# PERIPHERAL_CON.net
KiCad netlist of a schematic drawn in Altium Designer
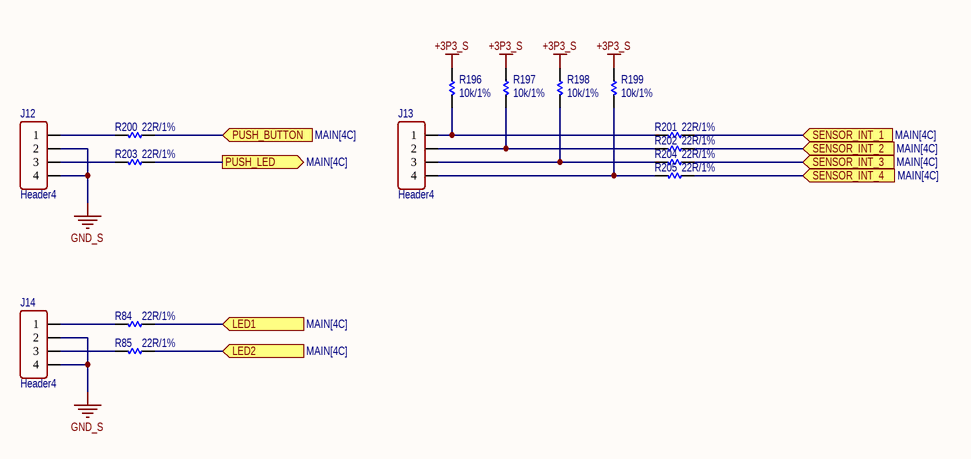
[diagram p0: PERIPHERAL_CON.SchDoc]

(export (version "E")
  (design (tool "Eeschema 10.0.6"))
  (components
    (comp (ref "J12")
      (value "Header4")
      (footprint "XH2.54-4-DIP")
      (description "Connector 4")
      (fields
        (field (name "MANUFACTURER") "Würth Elektronik eiSos GmbH")
        (field (name "PARTNO") "613002143121")
        (field (name "CREATED BY") "Karrer Zheng")
      )
      (libsource (lib "Library") (part "Header4"))
    )
    (comp (ref "J13")
      (value "Header4")
      (footprint "XH2.54-4-DIP")
      (description "Connector 4")
      (fields
        (field (name "MANUFACTURER") "Würth Elektronik eiSos GmbH")
        (field (name "PARTNO") "613002143121")
        (field (name "CREATED BY") "Karrer Zheng")
      )
      (libsource (lib "Library") (part "Header4"))
    )
    (comp (ref "J14")
      (value "Header4")
      (footprint "XH2.54-4-DIP")
      (description "Connector 4")
      (fields
        (field (name "MANUFACTURER") "Würth Elektronik eiSos GmbH")
        (field (name "PARTNO") "613002143121")
        (field (name "CREATED BY") "Karrer Zheng")
      )
      (libsource (lib "Library") (part "Header4"))
    )
    (comp (ref "R84")
      (value "22R/1%")
      (footprint "RES-SMD-0603")
      (description "RES SMD 22 OHM 1% 1/10W 0603")
      (libsource (lib "Library") (part "Res-SMD"))
    )
    (comp (ref "R85")
      (value "22R/1%")
      (footprint "RES-SMD-0603")
      (description "RES SMD 22 OHM 1% 1/10W 0603")
      (libsource (lib "Library") (part "Res-SMD"))
    )
    (comp (ref "R196")
      (value "10k/1%")
      (footprint "RES-SMD-0603")
      (description "RES SMD 10K OHM 1% 1/10W 0603")
      (fields
        (field (name "MANUFACTURER") "Generic Components")
        (field (name "PUBLISHER") "Altium Hobart Technology Centre")
      )
      (libsource (lib "Library") (part "Res-SMD"))
    )
    (comp (ref "R197")
      (value "10k/1%")
      (footprint "RES-SMD-0603")
      (description "RES SMD 10K OHM 1% 1/10W 0603")
      (fields
        (field (name "MANUFACTURER") "Generic Components")
        (field (name "PUBLISHER") "Altium Hobart Technology Centre")
      )
      (libsource (lib "Library") (part "Res-SMD"))
    )
    (comp (ref "R198")
      (value "10k/1%")
      (footprint "RES-SMD-0603")
      (description "RES SMD 10K OHM 1% 1/10W 0603")
      (fields
        (field (name "MANUFACTURER") "Generic Components")
        (field (name "PUBLISHER") "Altium Hobart Technology Centre")
      )
      (libsource (lib "Library") (part "Res-SMD"))
    )
    (comp (ref "R199")
      (value "10k/1%")
      (footprint "RES-SMD-0603")
      (description "RES SMD 10K OHM 1% 1/10W 0603")
      (fields
        (field (name "MANUFACTURER") "Generic Components")
        (field (name "PUBLISHER") "Altium Hobart Technology Centre")
      )
      (libsource (lib "Library") (part "Res-SMD"))
    )
    (comp (ref "R200")
      (value "22R/1%")
      (footprint "RES-SMD-0603")
      (description "RES SMD 22 OHM 1% 1/10W 0603")
      (libsource (lib "Library") (part "Res-SMD"))
    )
    (comp (ref "R201")
      (value "22R/1%")
      (footprint "RES-SMD-0603")
      (description "RES SMD 22 OHM 1% 1/10W 0603")
      (libsource (lib "Library") (part "Res-SMD"))
    )
    (comp (ref "R202")
      (value "22R/1%")
      (footprint "RES-SMD-0603")
      (description "RES SMD 22 OHM 1% 1/10W 0603")
      (libsource (lib "Library") (part "Res-SMD"))
    )
    (comp (ref "R203")
      (value "22R/1%")
      (footprint "RES-SMD-0603")
      (description "RES SMD 22 OHM 1% 1/10W 0603")
      (libsource (lib "Library") (part "Res-SMD"))
    )
    (comp (ref "R204")
      (value "22R/1%")
      (footprint "RES-SMD-0603")
      (description "RES SMD 22 OHM 1% 1/10W 0603")
      (libsource (lib "Library") (part "Res-SMD"))
    )
    (comp (ref "R205")
      (value "22R/1%")
      (footprint "RES-SMD-0603")
      (description "RES SMD 22 OHM 1% 1/10W 0603")
      (libsource (lib "Library") (part "Res-SMD"))
    )
  )
  (nets
    (net (code "1") (name "+3P3_S") (class "Default")
      (node (ref "R196") (pin "1") (pinfunction "1_1") (pintype "passive"))
      (node (ref "R197") (pin "1") (pinfunction "1_1") (pintype "passive"))
      (node (ref "R198") (pin "1") (pinfunction "1_1") (pintype "passive"))
      (node (ref "R199") (pin "1") (pinfunction "1_1") (pintype "passive"))
    )
    (net (code "2") (name "/LED1") (class "Default")
      (node (ref "R84") (pin "1") (pinfunction "1_1") (pintype "passive"))
    )
    (net (code "3") (name "/LED2") (class "Default")
      (node (ref "R85") (pin "1") (pinfunction "1_1") (pintype "passive"))
    )
    (net (code "4") (name "/PUSH_BUTTON") (class "Default")
      (node (ref "R200") (pin "1") (pinfunction "1_1") (pintype "passive"))
    )
    (net (code "5") (name "/PUSH_LED") (class "Default")
      (node (ref "R203") (pin "1") (pinfunction "1_1") (pintype "passive"))
    )
    (net (code "6") (name "/SENSOR_INT_1") (class "Default")
      (node (ref "R201") (pin "1") (pinfunction "1_1") (pintype "passive"))
    )
    (net (code "7") (name "/SENSOR_INT_2") (class "Default")
      (node (ref "R202") (pin "1") (pinfunction "1_1") (pintype "passive"))
    )
    (net (code "8") (name "/SENSOR_INT_3") (class "Default")
      (node (ref "R204") (pin "1") (pinfunction "1_1") (pintype "passive"))
    )
    (net (code "9") (name "/SENSOR_INT_4") (class "Default")
      (node (ref "R205") (pin "1") (pinfunction "1_1") (pintype "passive"))
    )
    (net (code "10") (name "GND_S") (class "Default")
      (node (ref "J12") (pin "2") (pinfunction "2_2") (pintype "passive"))
      (node (ref "J12") (pin "4") (pinfunction "4_4") (pintype "passive"))
      (node (ref "J14") (pin "2") (pinfunction "2_2") (pintype "passive"))
      (node (ref "J14") (pin "4") (pinfunction "4_4") (pintype "passive"))
    )
    (net (code "11") (name "Net-(J12-Pad1)") (class "Default")
      (node (ref "J12") (pin "1") (pinfunction "1_1") (pintype "passive"))
      (node (ref "R200") (pin "2") (pinfunction "2_2") (pintype "passive"))
    )
    (net (code "12") (name "Net-(J12-Pad3)") (class "Default")
      (node (ref "J12") (pin "3") (pinfunction "3_3") (pintype "passive"))
      (node (ref "R203") (pin "2") (pinfunction "2_2") (pintype "passive"))
    )
    (net (code "13") (name "Net-(J13-Pad1)") (class "Default")
      (node (ref "J13") (pin "1") (pinfunction "1_1") (pintype "passive"))
      (node (ref "R196") (pin "2") (pinfunction "2_2") (pintype "passive"))
      (node (ref "R201") (pin "2") (pinfunction "2_2") (pintype "passive"))
    )
    (net (code "14") (name "Net-(J13-Pad2)") (class "Default")
      (node (ref "J13") (pin "2") (pinfunction "2_2") (pintype "passive"))
      (node (ref "R197") (pin "2") (pinfunction "2_2") (pintype "passive"))
      (node (ref "R202") (pin "2") (pinfunction "2_2") (pintype "passive"))
    )
    (net (code "15") (name "Net-(J13-Pad3)") (class "Default")
      (node (ref "J13") (pin "3") (pinfunction "3_3") (pintype "passive"))
      (node (ref "R198") (pin "2") (pinfunction "2_2") (pintype "passive"))
      (node (ref "R204") (pin "2") (pinfunction "2_2") (pintype "passive"))
    )
    (net (code "16") (name "Net-(J13-Pad4)") (class "Default")
      (node (ref "J13") (pin "4") (pinfunction "4_4") (pintype "passive"))
      (node (ref "R199") (pin "2") (pinfunction "2_2") (pintype "passive"))
      (node (ref "R205") (pin "2") (pinfunction "2_2") (pintype "passive"))
    )
    (net (code "17") (name "Net-(J14-Pad1)") (class "Default")
      (node (ref "J14") (pin "1") (pinfunction "1_1") (pintype "passive"))
      (node (ref "R84") (pin "2") (pinfunction "2_2") (pintype "passive"))
    )
    (net (code "18") (name "Net-(J14-Pad3)") (class "Default")
      (node (ref "J14") (pin "3") (pinfunction "3_3") (pintype "passive"))
      (node (ref "R85") (pin "2") (pinfunction "2_2") (pintype "passive"))
    )
  )
)
